# WaterbedSlave.net
KiCad netlist of a schematic drawn in EAGLE
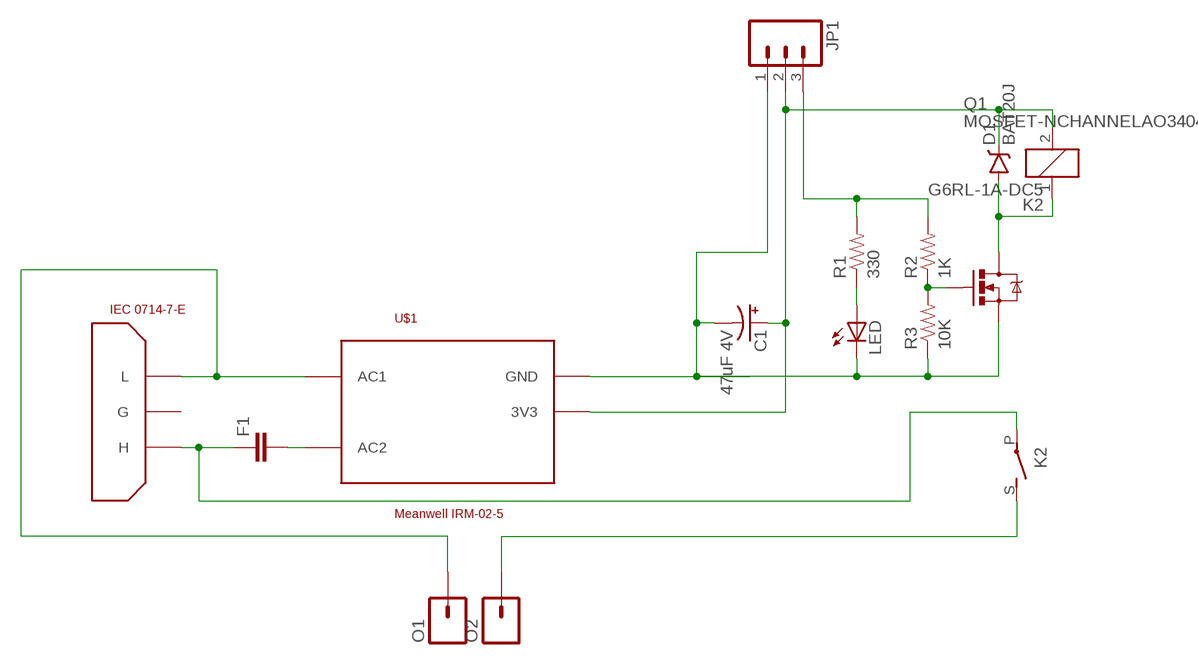
[diagram p0: schematic, sheet 1]

(export (version "E")
  (design (tool "Eeschema 10.0.6"))
  (components
    (comp (ref "C1")
      (value "47uF 4V")
      (footprint "eagle-import:CPOL-RADIAL-10UF-25V")
      (libsource (lib "eagle-import") (part "CAP_POLPTH2"))
    )
    (comp (ref "D1")
      (value "BAT20J")
      (footprint "eagle-import:SOD-323")
      (libsource (lib "eagle-import") (part "DIODE-SCHOTTKY-BAT20J"))
    )
    (comp (ref "F1")
      (value "CAPPTH1")
      (footprint "eagle-import:CAP-PTH-5MM")
      (libsource (lib "eagle-import") (part "CAPPTH1"))
    )
    (comp (ref "JP1")
      (value "M03POLAR_LOCK")
      (footprint "eagle-import:MOLEX-1X3_LOCK")
      (libsource (lib "eagle-import") (part "M03POLAR_LOCK"))
    )
    (comp (ref "K2")
      (value "G6RL-1A-DC5")
      (footprint "eagle-import:G6RS")
      (libsource (lib "eagle-import") (part "G6RS"))
    )
    (comp (ref "LED")
      (value "LEDCHIPLED_0805")
      (footprint "eagle-import:CHIPLED_0805")
      (libsource (lib "eagle-import") (part "LEDCHIPLED_0805"))
    )
    (comp (ref "O1")
      (value "M01PTH_2MM")
      (footprint "eagle-import:1X01_2MM")
      (libsource (lib "eagle-import") (part "M01PTH_2MM"))
    )
    (comp (ref "O2")
      (value "M01PTH_2MM")
      (footprint "eagle-import:1X01_2MM")
      (libsource (lib "eagle-import") (part "M01PTH_2MM"))
    )
    (comp (ref "Q1")
      (value "MOSFET-NCHANNELAO3404A")
      (footprint "eagle-import:SOT23-3")
      (libsource (lib "eagle-import") (part "MOSFET-NCHANNELAO3404A"))
    )
    (comp (ref "R1")
      (value "330")
      (footprint "eagle-import:0805")
      (libsource (lib "eagle-import") (part "RESISTOR0805-RES"))
    )
    (comp (ref "R2")
      (value "1K")
      (footprint "eagle-import:0805")
      (libsource (lib "eagle-import") (part "RESISTOR0805-RES"))
    )
    (comp (ref "R3")
      (value "10K")
      (footprint "eagle-import:0805")
      (libsource (lib "eagle-import") (part "RESISTOR0805-RES"))
    )
    (comp (ref "U$1")
      (value "Meanwell IRM-02-5")
      (footprint "eagle-import:RAC02-3.3SC")
      (libsource (lib "eagle-import") (part "RAC02-3.3SC"))
    )
    (comp (ref "U$3")
      (value "IEC 0714-7-E")
      (footprint "eagle-import:IEC")
      (libsource (lib "eagle-import") (part "IEC"))
    )
  )
  (nets
    (net (code "1") (name "Net-(C1-+)") (class "Default")
      (node (ref "C1") (pin "1") (pinfunction "+_1") (pintype "passive"))
      (node (ref "D1") (pin "C") (pinfunction "C_C") (pintype "passive"))
      (node (ref "JP1") (pin "2") (pinfunction "2_2") (pintype "passive"))
      (node (ref "K2") (pin "2") (pinfunction "2_2") (pintype "passive"))
      (node (ref "U$1") (pin "GND") (pinfunction "3V3_GND") (pintype "bidirectional"))
    )
    (net (code "2") (name "Net-(C1--)") (class "Default")
      (node (ref "C1") (pin "2") (pinfunction "-_2") (pintype "passive"))
      (node (ref "JP1") (pin "1") (pinfunction "1_1") (pintype "passive"))
      (node (ref "LED") (pin "C") (pinfunction "C_C") (pintype "passive"))
      (node (ref "Q1") (pin "2") (pinfunction "S_2") (pintype "passive"))
      (node (ref "R3") (pin "1") (pinfunction "1_1") (pintype "passive"))
      (node (ref "U$1") (pin "3V3") (pinfunction "GND_3V3") (pintype "bidirectional"))
    )
    (net (code "3") (name "Net-(F1-Pad1)") (class "Default")
      (node (ref "F1") (pin "1") (pinfunction "1_1") (pintype "passive"))
      (node (ref "K2") (pin "P") (pinfunction "P_P") (pintype "passive"))
      (node (ref "U$3") (pin "H") (pinfunction "H_H") (pintype "power_in"))
    )
    (net (code "4") (name "Net-(F1-Pad2)") (class "Default")
      (node (ref "F1") (pin "2") (pinfunction "2_2") (pintype "passive"))
      (node (ref "U$1") (pin "AC2") (pinfunction "AC2_AC2") (pintype "bidirectional"))
    )
    (net (code "5") (name "Net-(JP1-Pad3)") (class "Default")
      (node (ref "JP1") (pin "3") (pinfunction "3_3") (pintype "passive"))
      (node (ref "R1") (pin "2") (pinfunction "2_2") (pintype "passive"))
      (node (ref "R2") (pin "2") (pinfunction "2_2") (pintype "passive"))
    )
    (net (code "6") (name "Net-(K2-PadS)") (class "Default")
      (node (ref "K2") (pin "S") (pinfunction "S_S") (pintype "passive"))
      (node (ref "O2") (pin "1") (pinfunction "1_1") (pintype "passive"))
    )
    (net (code "7") (name "Net-(LED-PadA)") (class "Default")
      (node (ref "LED") (pin "A") (pinfunction "A_A") (pintype "passive"))
      (node (ref "R1") (pin "1") (pinfunction "1_1") (pintype "passive"))
    )
    (net (code "8") (name "Net-(O1-Pad1)") (class "Default")
      (node (ref "O1") (pin "1") (pinfunction "1_1") (pintype "passive"))
      (node (ref "U$1") (pin "AC1") (pinfunction "AC1_AC1") (pintype "bidirectional"))
      (node (ref "U$3") (pin "L") (pinfunction "L_L") (pintype "power_in"))
    )
    (net (code "9") (name "Net-(Q1-D)") (class "Default")
      (node (ref "D1") (pin "A") (pinfunction "A_A") (pintype "passive"))
      (node (ref "K2") (pin "1") (pinfunction "1_1") (pintype "passive"))
      (node (ref "Q1") (pin "3") (pinfunction "D_3") (pintype "passive"))
    )
    (net (code "10") (name "Net-(Q1-G)") (class "Default")
      (node (ref "Q1") (pin "1") (pinfunction "G_1") (pintype "passive"))
      (node (ref "R2") (pin "1") (pinfunction "1_1") (pintype "passive"))
      (node (ref "R3") (pin "2") (pinfunction "2_2") (pintype "passive"))
    )
    (net (code "11") (name "unconnected-(U$3-PadG)") (class "Default")
      (node (ref "U$3") (pin "G") (pinfunction "G_G") (pintype "passive"))
    )
  )
)
